# DC309A_Pinout.net
KiCad netlist of a schematic drawn in Altium Designer
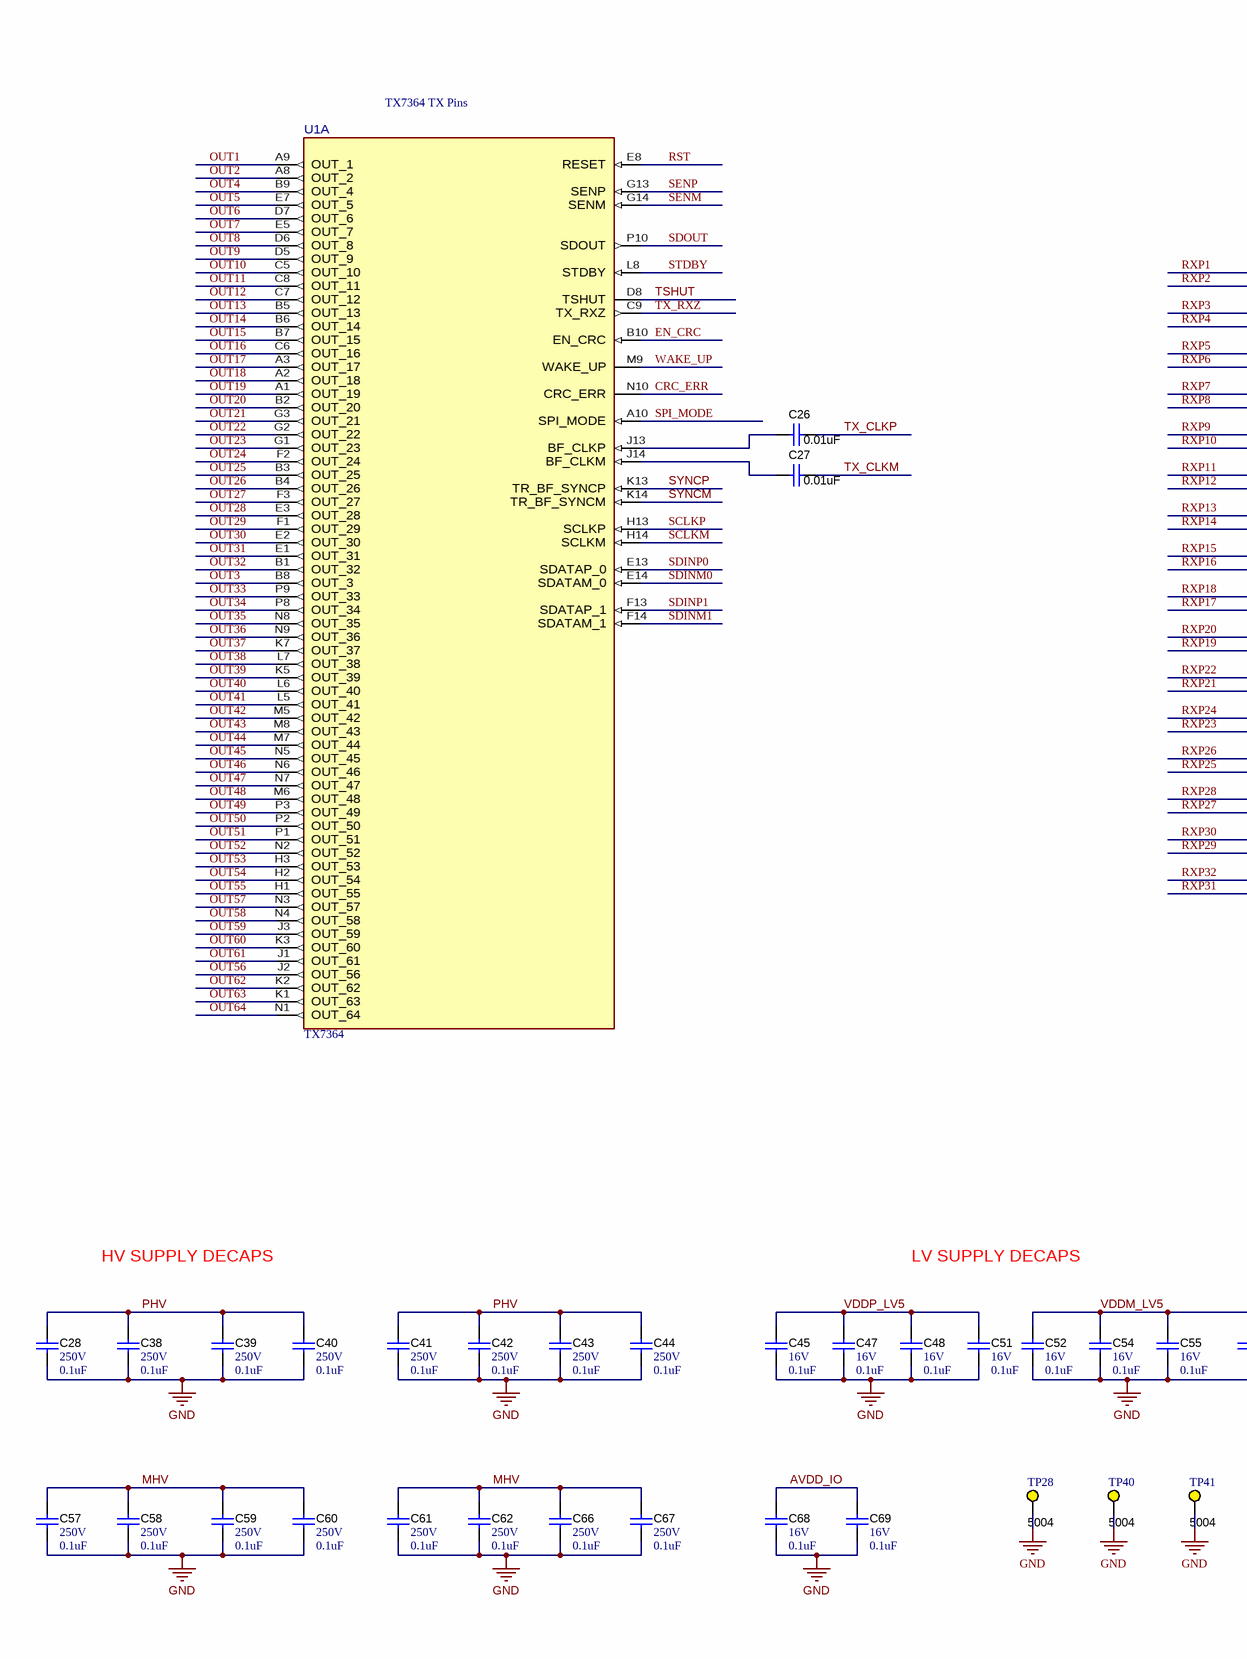
[diagram p0: DC309A_Pinout.SchDoc, left]
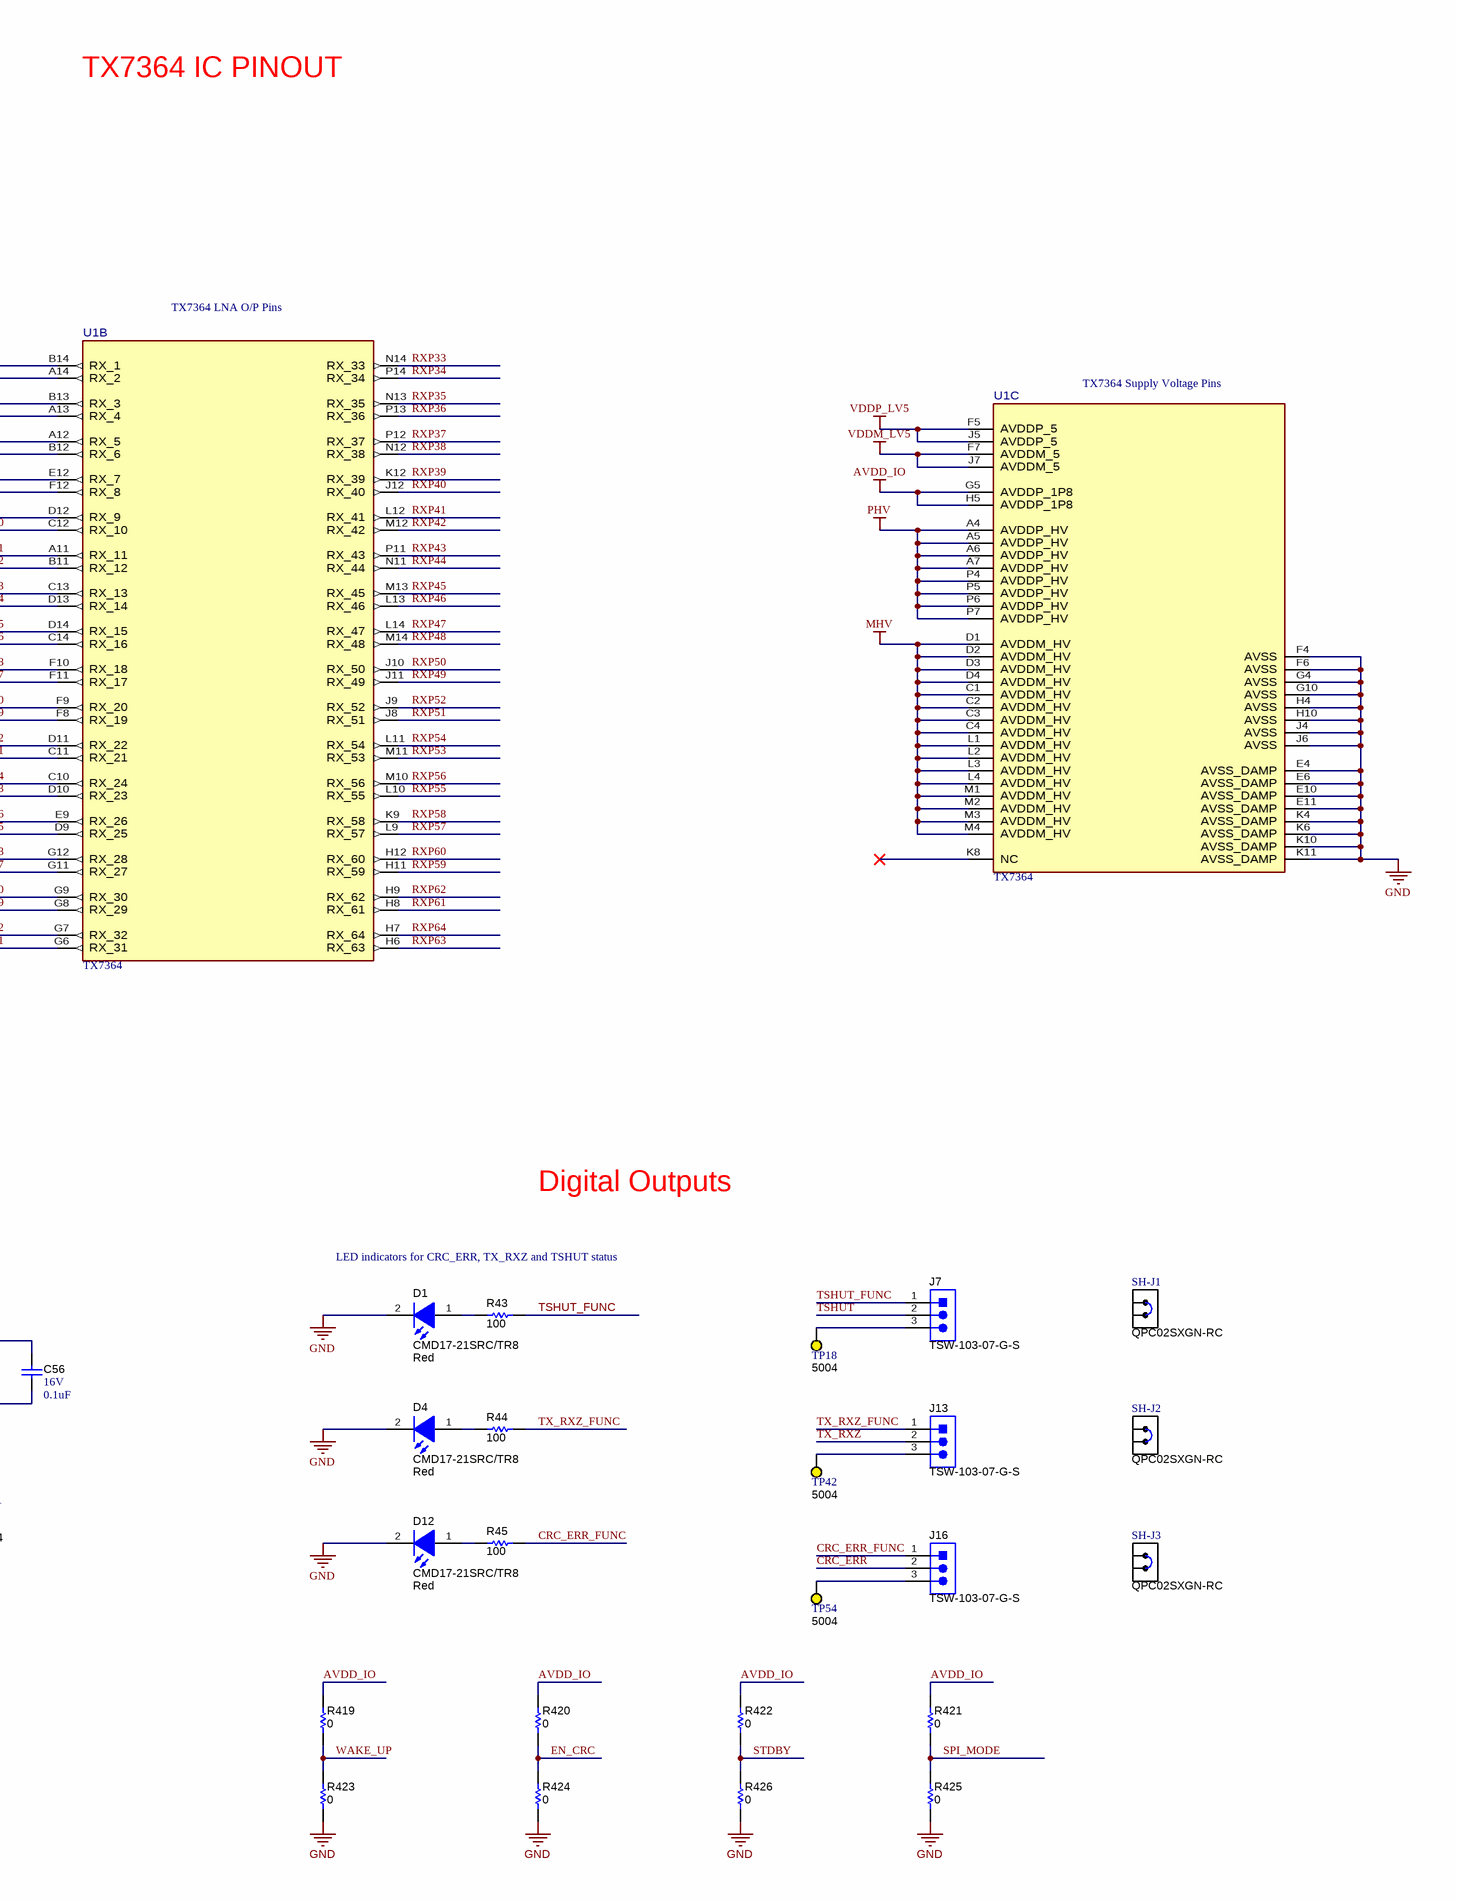
[diagram p1: DC309A_Pinout.SchDoc, right]

(export (version "E")
  (design (tool "Eeschema 10.0.6"))
  (components
    (comp (ref "C26")
      (value "520L103KT16T")
      (footprint "0402_065")
      (description "CAP, CERM, 0.01 uF, 16 V, +/- 10%, X7R, 0402")
      (fields (field (name "MANUFACTURER") "AT Ceramics") (field (name "VALUEDISPLAYED") "0.01uF"))
      (libsource (lib "Altium Vault - TI") (part "CMP-0006210-2"))
    )
    (comp (ref "C27")
      (value "520L103KT16T")
      (footprint "0402_065")
      (description "CAP, CERM, 0.01 uF, 16 V, +/- 10%, X7R, 0402")
      (fields (field (name "MANUFACTURER") "AT Ceramics") (field (name "VALUEDISPLAYED") "0.01uF"))
      (libsource (lib "Altium Vault - TI") (part "CMP-0006210-2"))
    )
    (comp (ref "C28")
      (value "C2012X7T2E104K125AA")
      (footprint "0805_HV")
      (description "CAP, CERM, 0.1 uF, 250 V, +/- 10%, X7T, 0805")
      (fields
        (field (name "MANUFACTURER") "TDK")
        (field (name "VDC_V") "250V")
        (field (name "VALUEDISPLAYED") "0.1uF")
      )
      (libsource (lib "Altium Vault - TI") (part "Capacitor"))
    )
    (comp (ref "C38")
      (value "C2012X7T2E104K125AA")
      (footprint "0805_HV")
      (description "CAP, CERM, 0.1 uF, 250 V, +/- 10%, X7T, 0805")
      (fields
        (field (name "MANUFACTURER") "TDK")
        (field (name "VDC_V") "250V")
        (field (name "VALUEDISPLAYED") "0.1uF")
      )
      (libsource (lib "Altium Vault - TI") (part "Capacitor"))
    )
    (comp (ref "C39")
      (value "C2012X7T2E104K125AA")
      (footprint "0805_HV")
      (description "CAP, CERM, 0.1 uF, 250 V, +/- 10%, X7T, 0805")
      (fields
        (field (name "MANUFACTURER") "TDK")
        (field (name "VDC_V") "250V")
        (field (name "VALUEDISPLAYED") "0.1uF")
      )
      (libsource (lib "Altium Vault - TI") (part "Capacitor"))
    )
    (comp (ref "C40")
      (value "C2012X7T2E104K125AA")
      (footprint "0805_HV")
      (description "CAP, CERM, 0.1 uF, 250 V, +/- 10%, X7T, 0805")
      (fields
        (field (name "MANUFACTURER") "TDK")
        (field (name "VDC_V") "250V")
        (field (name "VALUEDISPLAYED") "0.1uF")
      )
      (libsource (lib "Altium Vault - TI") (part "Capacitor"))
    )
    (comp (ref "C41")
      (value "C2012X7T2E104K125AA")
      (footprint "0805_HV")
      (description "CAP, CERM, 0.1 uF, 250 V, +/- 10%, X7T, 0805")
      (fields
        (field (name "MANUFACTURER") "TDK")
        (field (name "VDC_V") "250V")
        (field (name "VALUEDISPLAYED") "0.1uF")
      )
      (libsource (lib "Altium Vault - TI") (part "Capacitor"))
    )
    (comp (ref "C42")
      (value "C2012X7T2E104K125AA")
      (footprint "0805_HV")
      (description "CAP, CERM, 0.1 uF, 250 V, +/- 10%, X7T, 0805")
      (fields
        (field (name "MANUFACTURER") "TDK")
        (field (name "VDC_V") "250V")
        (field (name "VALUEDISPLAYED") "0.1uF")
      )
      (libsource (lib "Altium Vault - TI") (part "Capacitor"))
    )
    (comp (ref "C43")
      (value "C2012X7T2E104K125AA")
      (footprint "0805_HV")
      (description "CAP, CERM, 0.1 uF, 250 V, +/- 10%, X7T, 0805")
      (fields
        (field (name "MANUFACTURER") "TDK")
        (field (name "VDC_V") "250V")
        (field (name "VALUEDISPLAYED") "0.1uF")
      )
      (libsource (lib "Altium Vault - TI") (part "Capacitor"))
    )
    (comp (ref "C44")
      (value "C2012X7T2E104K125AA")
      (footprint "0805_HV")
      (description "CAP, CERM, 0.1 uF, 250 V, +/- 10%, X7T, 0805")
      (fields
        (field (name "MANUFACTURER") "TDK")
        (field (name "VDC_V") "250V")
        (field (name "VALUEDISPLAYED") "0.1uF")
      )
      (libsource (lib "Altium Vault - TI") (part "Capacitor"))
    )
    (comp (ref "C45")
      (value "C0603X6S1C104K030BC")
      (footprint "0201_033")
      (description "CAP, CERM, 0.1 uF, 16 V, +/- 10%, X6S, 0201")
      (fields
        (field (name "MANUFACTURER") "TDK")
        (field (name "VDC_V") "16V")
        (field (name "VALUEDISPLAYED") "0.1uF")
      )
      (libsource (lib "Altium Vault - TI") (part "Capacitor"))
    )
    (comp (ref "C47")
      (value "C0603X6S1C104K030BC")
      (footprint "0201_033")
      (description "CAP, CERM, 0.1 uF, 16 V, +/- 10%, X6S, 0201")
      (fields
        (field (name "MANUFACTURER") "TDK")
        (field (name "VDC_V") "16V")
        (field (name "VALUEDISPLAYED") "0.1uF")
      )
      (libsource (lib "Altium Vault - TI") (part "Capacitor"))
    )
    (comp (ref "C48")
      (value "C0603X6S1C104K030BC")
      (footprint "0201_033")
      (description "CAP, CERM, 0.1 uF, 16 V, +/- 10%, X6S, 0201")
      (fields
        (field (name "MANUFACTURER") "TDK")
        (field (name "VDC_V") "16V")
        (field (name "VALUEDISPLAYED") "0.1uF")
      )
      (libsource (lib "Altium Vault - TI") (part "Capacitor"))
    )
    (comp (ref "C51")
      (value "C0603X6S1C104K030BC")
      (footprint "0201_033")
      (description "CAP, CERM, 0.1 uF, 16 V, +/- 10%, X6S, 0201")
      (fields
        (field (name "MANUFACTURER") "TDK")
        (field (name "VDC_V") "16V")
        (field (name "VALUEDISPLAYED") "0.1uF")
      )
      (libsource (lib "Altium Vault - TI") (part "Capacitor"))
    )
    (comp (ref "C52")
      (value "C0603X6S1C104K030BC")
      (footprint "0201_033")
      (description "CAP, CERM, 0.1 uF, 16 V, +/- 10%, X6S, 0201")
      (fields
        (field (name "MANUFACTURER") "TDK")
        (field (name "VDC_V") "16V")
        (field (name "VALUEDISPLAYED") "0.1uF")
      )
      (libsource (lib "Altium Vault - TI") (part "Capacitor"))
    )
    (comp (ref "C54")
      (value "C0603X6S1C104K030BC")
      (footprint "0201_033")
      (description "CAP, CERM, 0.1 uF, 16 V, +/- 10%, X6S, 0201")
      (fields
        (field (name "MANUFACTURER") "TDK")
        (field (name "VDC_V") "16V")
        (field (name "VALUEDISPLAYED") "0.1uF")
      )
      (libsource (lib "Altium Vault - TI") (part "Capacitor"))
    )
    (comp (ref "C55")
      (value "C0603X6S1C104K030BC")
      (footprint "0201_033")
      (description "CAP, CERM, 0.1 uF, 16 V, +/- 10%, X6S, 0201")
      (fields
        (field (name "MANUFACTURER") "TDK")
        (field (name "VDC_V") "16V")
        (field (name "VALUEDISPLAYED") "0.1uF")
      )
      (libsource (lib "Altium Vault - TI") (part "Capacitor"))
    )
    (comp (ref "C56")
      (value "C0603X6S1C104K030BC")
      (footprint "0201_033")
      (description "CAP, CERM, 0.1 uF, 16 V, +/- 10%, X6S, 0201")
      (fields
        (field (name "MANUFACTURER") "TDK")
        (field (name "VDC_V") "16V")
        (field (name "VALUEDISPLAYED") "0.1uF")
      )
      (libsource (lib "Altium Vault - TI") (part "Capacitor"))
    )
    (comp (ref "C57")
      (value "C2012X7T2E104K125AA")
      (footprint "0805_HV")
      (description "CAP, CERM, 0.1 uF, 250 V, +/- 10%, X7T, 0805")
      (fields
        (field (name "MANUFACTURER") "TDK")
        (field (name "VDC_V") "250V")
        (field (name "VALUEDISPLAYED") "0.1uF")
      )
      (libsource (lib "Altium Vault - TI") (part "Capacitor"))
    )
    (comp (ref "C58")
      (value "C2012X7T2E104K125AA")
      (footprint "0805_HV")
      (description "CAP, CERM, 0.1 uF, 250 V, +/- 10%, X7T, 0805")
      (fields
        (field (name "MANUFACTURER") "TDK")
        (field (name "VDC_V") "250V")
        (field (name "VALUEDISPLAYED") "0.1uF")
      )
      (libsource (lib "Altium Vault - TI") (part "Capacitor"))
    )
    (comp (ref "C59")
      (value "C2012X7T2E104K125AA")
      (footprint "0805_HV")
      (description "CAP, CERM, 0.1 uF, 250 V, +/- 10%, X7T, 0805")
      (fields
        (field (name "MANUFACTURER") "TDK")
        (field (name "VDC_V") "250V")
        (field (name "VALUEDISPLAYED") "0.1uF")
      )
      (libsource (lib "Altium Vault - TI") (part "Capacitor"))
    )
    (comp (ref "C60")
      (value "C2012X7T2E104K125AA")
      (footprint "0805_HV")
      (description "CAP, CERM, 0.1 uF, 250 V, +/- 10%, X7T, 0805")
      (fields
        (field (name "MANUFACTURER") "TDK")
        (field (name "VDC_V") "250V")
        (field (name "VALUEDISPLAYED") "0.1uF")
      )
      (libsource (lib "Altium Vault - TI") (part "Capacitor"))
    )
    (comp (ref "C61")
      (value "C2012X7T2E104K125AA")
      (footprint "0805_HV")
      (description "CAP, CERM, 0.1 uF, 250 V, +/- 10%, X7T, 0805")
      (fields
        (field (name "MANUFACTURER") "TDK")
        (field (name "VDC_V") "250V")
        (field (name "VALUEDISPLAYED") "0.1uF")
      )
      (libsource (lib "Altium Vault - TI") (part "Capacitor"))
    )
    (comp (ref "C62")
      (value "C2012X7T2E104K125AA")
      (footprint "0805_HV")
      (description "CAP, CERM, 0.1 uF, 250 V, +/- 10%, X7T, 0805")
      (fields
        (field (name "MANUFACTURER") "TDK")
        (field (name "VDC_V") "250V")
        (field (name "VALUEDISPLAYED") "0.1uF")
      )
      (libsource (lib "Altium Vault - TI") (part "Capacitor"))
    )
    (comp (ref "C66")
      (value "C2012X7T2E104K125AA")
      (footprint "0805_HV")
      (description "CAP, CERM, 0.1 uF, 250 V, +/- 10%, X7T, 0805")
      (fields
        (field (name "MANUFACTURER") "TDK")
        (field (name "VDC_V") "250V")
        (field (name "VALUEDISPLAYED") "0.1uF")
      )
      (libsource (lib "Altium Vault - TI") (part "Capacitor"))
    )
    (comp (ref "C67")
      (value "C2012X7T2E104K125AA")
      (footprint "0805_HV")
      (description "CAP, CERM, 0.1 uF, 250 V, +/- 10%, X7T, 0805")
      (fields
        (field (name "MANUFACTURER") "TDK")
        (field (name "VDC_V") "250V")
        (field (name "VALUEDISPLAYED") "0.1uF")
      )
      (libsource (lib "Altium Vault - TI") (part "Capacitor"))
    )
    (comp (ref "C68")
      (value "C0603X6S1C104K030BC")
      (footprint "0201_033")
      (description "CAP, CERM, 0.1 uF, 16 V, +/- 10%, X6S, 0201")
      (fields
        (field (name "MANUFACTURER") "TDK")
        (field (name "VDC_V") "16V")
        (field (name "VALUEDISPLAYED") "0.1uF")
      )
      (libsource (lib "Altium Vault - TI") (part "Capacitor"))
    )
    (comp (ref "C69")
      (value "C0603X6S1C104K030BC")
      (footprint "0201_033")
      (description "CAP, CERM, 0.1 uF, 16 V, +/- 10%, X6S, 0201")
      (fields
        (field (name "MANUFACTURER") "TDK")
        (field (name "VDC_V") "16V")
        (field (name "VALUEDISPLAYED") "0.1uF")
      )
      (libsource (lib "Altium Vault - TI") (part "Capacitor"))
    )
    (comp (ref "D1")
      (value "CMD17-21SRC/TR8")
      (footprint "CMD17-21_Red")
      (description "LED, Red, SMD")
      (fields
        (field (name "ALTIUM_VALUE") "Red")
        (field (name "MANUFACTURER") "Visual Communications Company, LLC")
      )
      (libsource (lib "Altium Vault - TI") (part "CMP-0084855-1"))
    )
    (comp (ref "D4")
      (value "CMD17-21SRC/TR8")
      (footprint "CMD17-21_Red")
      (description "LED, Red, SMD")
      (fields
        (field (name "ALTIUM_VALUE") "Red")
        (field (name "MANUFACTURER") "Visual Communications Company, LLC")
      )
      (libsource (lib "Altium Vault - TI") (part "CMP-0084855-1"))
    )
    (comp (ref "D12")
      (value "CMD17-21SRC/TR8")
      (footprint "CMD17-21_Red")
      (description "LED, Red, SMD")
      (fields
        (field (name "ALTIUM_VALUE") "Red")
        (field (name "MANUFACTURER") "Visual Communications Company, LLC")
      )
      (libsource (lib "Altium Vault - TI") (part "CMP-0084855-1"))
    )
    (comp (ref "J7")
      (value "TSW-103-07-G-S")
      (footprint "TSW-103-07-G-S")
      (description "Header, 100mil, 3x1, Gold, TH")
      (fields (field (name "MANUFACTURER") "Samtec"))
      (libsource (lib "Altium Vault - TI") (part "Header_3x1"))
    )
    (comp (ref "J13")
      (value "TSW-103-07-G-S")
      (footprint "TSW-103-07-G-S")
      (description "Header, 100mil, 3x1, Gold, TH")
      (fields (field (name "MANUFACTURER") "Samtec"))
      (libsource (lib "Altium Vault - TI") (part "Header_3x1"))
    )
    (comp (ref "J16")
      (value "TSW-103-07-G-S")
      (footprint "TSW-103-07-G-S")
      (description "Header, 100mil, 3x1, Gold, TH")
      (fields (field (name "MANUFACTURER") "Samtec"))
      (libsource (lib "Altium Vault - TI") (part "Header_3x1"))
    )
    (comp (ref "R43")
      (value "Resistor")
      (footprint "0402")
      (description "RES, 100, 5%, 0.1 W, AEC-Q200 Grade 0, 0402")
      (fields
        (field (name "PARTNUMBER") "ERJ-2GEJ101X")
        (field (name "VALUEDISPLAYED") "100")
        (field (name "MANUFACTURER") "Panasonic")
      )
      (libsource (lib "Altium Vault - TI") (part "Resistor"))
    )
    (comp (ref "R44")
      (value "Resistor")
      (footprint "0402")
      (description "RES, 100, 5%, 0.1 W, AEC-Q200 Grade 0, 0402")
      (fields
        (field (name "PARTNUMBER") "ERJ-2GEJ101X")
        (field (name "VALUEDISPLAYED") "100")
        (field (name "MANUFACTURER") "Panasonic")
      )
      (libsource (lib "Altium Vault - TI") (part "Resistor"))
    )
    (comp (ref "R45")
      (value "Resistor")
      (footprint "0402")
      (description "RES, 100, 5%, 0.1 W, AEC-Q200 Grade 0, 0402")
      (fields
        (field (name "PARTNUMBER") "ERJ-2GEJ101X")
        (field (name "VALUEDISPLAYED") "100")
        (field (name "MANUFACTURER") "Panasonic")
      )
      (libsource (lib "Altium Vault - TI") (part "Resistor"))
    )
    (comp (ref "R419")
      (value "Resistor")
      (footprint "0402")
      (description "RES, 0, 5%, 0.1 W, AEC-Q200 Grade 0, 0402")
      (fields
        (field (name "PARTNUMBER") "ERJ-2GE0R00X")
        (field (name "MANUFACTURER") "Panasonic")
        (field (name "RES_OHM") "0")
      )
      (libsource (lib "Altium Vault - TI") (part "CMP-0026992-3"))
    )
    (comp (ref "R420")
      (value "Resistor")
      (footprint "0402")
      (description "RES, 0, 5%, 0.1 W, AEC-Q200 Grade 0, 0402")
      (fields
        (field (name "PARTNUMBER") "ERJ-2GE0R00X")
        (field (name "MANUFACTURER") "Panasonic")
        (field (name "RES_OHM") "0")
      )
      (libsource (lib "Altium Vault - TI") (part "CMP-0026992-3"))
    )
    (comp (ref "R421")
      (value "Resistor")
      (footprint "0402")
      (description "RES, 0, 5%, 0.1 W, AEC-Q200 Grade 0, 0402")
      (fields
        (field (name "PARTNUMBER") "ERJ-2GE0R00X")
        (field (name "MANUFACTURER") "Panasonic")
        (field (name "RES_OHM") "0")
      )
      (libsource (lib "Altium Vault - TI") (part "CMP-0026992-3"))
    )
    (comp (ref "R422")
      (value "Resistor")
      (footprint "0402")
      (description "RES, 0, 5%, 0.1 W, AEC-Q200 Grade 0, 0402")
      (fields
        (field (name "PARTNUMBER") "ERJ-2GE0R00X")
        (field (name "MANUFACTURER") "Panasonic")
        (field (name "RES_OHM") "0")
      )
      (libsource (lib "Altium Vault - TI") (part "CMP-0026992-3"))
    )
    (comp (ref "R423")
      (value "Resistor")
      (footprint "0402")
      (description "RES, 0, 5%, 0.1 W, AEC-Q200 Grade 0, 0402")
      (fields
        (field (name "PARTNUMBER") "ERJ-2GE0R00X")
        (field (name "MANUFACTURER") "Panasonic")
        (field (name "RES_OHM") "0")
      )
      (libsource (lib "Altium Vault - TI") (part "CMP-0026992-3"))
    )
    (comp (ref "R424")
      (value "Resistor")
      (footprint "0402")
      (description "RES, 0, 5%, 0.1 W, AEC-Q200 Grade 0, 0402")
      (fields
        (field (name "PARTNUMBER") "ERJ-2GE0R00X")
        (field (name "MANUFACTURER") "Panasonic")
        (field (name "RES_OHM") "0")
      )
      (libsource (lib "Altium Vault - TI") (part "CMP-0026992-3"))
    )
    (comp (ref "R425")
      (value "Resistor")
      (footprint "0402")
      (description "RES, 0, 5%, 0.1 W, AEC-Q200 Grade 0, 0402")
      (fields
        (field (name "PARTNUMBER") "ERJ-2GE0R00X")
        (field (name "MANUFACTURER") "Panasonic")
        (field (name "RES_OHM") "0")
      )
      (libsource (lib "Altium Vault - TI") (part "CMP-0026992-3"))
    )
    (comp (ref "R426")
      (value "Resistor")
      (footprint "0402")
      (description "RES, 0, 5%, 0.1 W, AEC-Q200 Grade 0, 0402")
      (fields
        (field (name "PARTNUMBER") "ERJ-2GE0R00X")
        (field (name "MANUFACTURER") "Panasonic")
        (field (name "RES_OHM") "0")
      )
      (libsource (lib "Altium Vault - TI") (part "CMP-0026992-3"))
    )
    (comp (ref "SH-J1")
      (value "QPC02SXGN-RC")
      (footprint "FP-QPC02SXGN-RC_JUMPER-MFG")
      (fields (field (name "MANUFACTURER") "Sullins"))
      (libsource (lib "Altium Vault - TI") (part "Shunt"))
    )
    (comp (ref "SH-J2")
      (value "QPC02SXGN-RC")
      (footprint "FP-QPC02SXGN-RC_JUMPER-MFG")
      (fields (field (name "MANUFACTURER") "Sullins"))
      (libsource (lib "Altium Vault - TI") (part "Shunt"))
    )
    (comp (ref "SH-J3")
      (value "QPC02SXGN-RC")
      (footprint "FP-QPC02SXGN-RC_JUMPER-MFG")
      (fields (field (name "MANUFACTURER") "Sullins"))
      (libsource (lib "Altium Vault - TI") (part "Shunt"))
    )
    (comp (ref "TP18")
      (value "5004")
      (footprint "Keystone5004")
      (description "Test Point, Miniature, Yellow, TH")
      (fields (field (name "MANUFACTURER") "Keystone Electronics"))
      (libsource (lib "Altium Vault - TI") (part "5004"))
    )
    (comp (ref "TP28")
      (value "5004")
      (footprint "Keystone5004")
      (description "Test Point, Miniature, Yellow, TH")
      (fields (field (name "MANUFACTURER") "Keystone Electronics"))
      (libsource (lib "Altium Vault - TI") (part "5004"))
    )
    (comp (ref "TP40")
      (value "5004")
      (footprint "Keystone5004")
      (description "Test Point, Miniature, Yellow, TH")
      (fields (field (name "MANUFACTURER") "Keystone Electronics"))
      (libsource (lib "Altium Vault - TI") (part "5004"))
    )
    (comp (ref "TP41")
      (value "5004")
      (footprint "Keystone5004")
      (description "Test Point, Miniature, Yellow, TH")
      (fields (field (name "MANUFACTURER") "Keystone Electronics"))
      (libsource (lib "Altium Vault - TI") (part "5004"))
    )
    (comp (ref "TP42")
      (value "5004")
      (footprint "Keystone5004")
      (description "Test Point, Miniature, Yellow, TH")
      (fields (field (name "MANUFACTURER") "Keystone Electronics"))
      (libsource (lib "Altium Vault - TI") (part "5004"))
    )
    (comp (ref "TP54")
      (value "5004")
      (footprint "Keystone5004")
      (description "Test Point, Miniature, Yellow, TH")
      (fields (field (name "MANUFACTURER") "Keystone Electronics"))
      (libsource (lib "Altium Vault - TI") (part "5004"))
    )
    (comp (ref "U1")
      (value "TX7364")
      (footprint "ACP0196A-MFG")
      (fields (field (name "PARTNUMBER") "TX7364") (field (name "MANUFACTURER") "Texas Instruments"))
      (libsource (lib "Altium Vault - TI") (part "SYM-TX7364"))
    )
  )
  (nets
    (net (code "1") (name "/CRC_ERR") (class "Default")
      (node (ref "J16") (pin "2") (pinfunction "2_2") (pintype "passive"))
      (node (ref "U1") (pin "N10") (pinfunction "CRC_ERR_N10") (pintype "passive"))
    )
    (net (code "2") (name "/CRC_ERR_FUNC") (class "Default")
      (node (ref "J16") (pin "1") (pinfunction "1_1") (pintype "passive"))
      (node (ref "R45") (pin "1") (pinfunction "1_1") (pintype "passive"))
    )
    (net (code "3") (name "/EN_CRC") (class "Default")
      (node (ref "R420") (pin "1") (pinfunction "1_1") (pintype "passive"))
      (node (ref "R424") (pin "2") (pinfunction "2_2") (pintype "passive"))
      (node (ref "U1") (pin "B10") (pinfunction "EN_CRC_B10") (pintype "input"))
    )
    (net (code "4") (name "/OUT1") (class "Default")
      (node (ref "U1") (pin "A9") (pinfunction "OUT_1_A9") (pintype "output"))
    )
    (net (code "5") (name "/OUT2") (class "Default")
      (node (ref "U1") (pin "A8") (pinfunction "OUT_2_A8") (pintype "output"))
    )
    (net (code "6") (name "/OUT3") (class "Default")
      (node (ref "U1") (pin "B8") (pinfunction "OUT_3_B8") (pintype "output"))
    )
    (net (code "7") (name "/OUT4") (class "Default")
      (node (ref "U1") (pin "B9") (pinfunction "OUT_4_B9") (pintype "output"))
    )
    (net (code "8") (name "/OUT5") (class "Default")
      (node (ref "U1") (pin "E7") (pinfunction "OUT_5_E7") (pintype "output"))
    )
    (net (code "9") (name "/OUT6") (class "Default")
      (node (ref "U1") (pin "D7") (pinfunction "OUT_6_D7") (pintype "output"))
    )
    (net (code "10") (name "/OUT7") (class "Default")
      (node (ref "U1") (pin "E5") (pinfunction "OUT_7_E5") (pintype "output"))
    )
    (net (code "11") (name "/OUT8") (class "Default")
      (node (ref "U1") (pin "D6") (pinfunction "OUT_8_D6") (pintype "output"))
    )
    (net (code "12") (name "/OUT9") (class "Default")
      (node (ref "U1") (pin "D5") (pinfunction "OUT_9_D5") (pintype "output"))
    )
    (net (code "13") (name "/OUT10") (class "Default")
      (node (ref "U1") (pin "C5") (pinfunction "OUT_10_C5") (pintype "output"))
    )
    (net (code "14") (name "/OUT11") (class "Default")
      (node (ref "U1") (pin "C8") (pinfunction "OUT_11_C8") (pintype "output"))
    )
    (net (code "15") (name "/OUT12") (class "Default")
      (node (ref "U1") (pin "C7") (pinfunction "OUT_12_C7") (pintype "output"))
    )
    (net (code "16") (name "/OUT13") (class "Default")
      (node (ref "U1") (pin "B5") (pinfunction "OUT_13_B5") (pintype "output"))
    )
    (net (code "17") (name "/OUT14") (class "Default")
      (node (ref "U1") (pin "B6") (pinfunction "OUT_14_B6") (pintype "output"))
    )
    (net (code "18") (name "/OUT15") (class "Default")
      (node (ref "U1") (pin "B7") (pinfunction "OUT_15_B7") (pintype "output"))
    )
    (net (code "19") (name "/OUT16") (class "Default")
      (node (ref "U1") (pin "C6") (pinfunction "OUT_16_C6") (pintype "output"))
    )
    (net (code "20") (name "/OUT17") (class "Default")
      (node (ref "U1") (pin "A3") (pinfunction "OUT_17_A3") (pintype "output"))
    )
    (net (code "21") (name "/OUT18") (class "Default")
      (node (ref "U1") (pin "A2") (pinfunction "OUT_18_A2") (pintype "output"))
    )
    (net (code "22") (name "/OUT19") (class "Default")
      (node (ref "U1") (pin "A1") (pinfunction "OUT_19_A1") (pintype "output"))
    )
    (net (code "23") (name "/OUT20") (class "Default")
      (node (ref "U1") (pin "B2") (pinfunction "OUT_20_B2") (pintype "output"))
    )
    (net (code "24") (name "/OUT21") (class "Default")
      (node (ref "U1") (pin "G3") (pinfunction "OUT_21_G3") (pintype "output"))
    )
    (net (code "25") (name "/OUT22") (class "Default")
      (node (ref "U1") (pin "G2") (pinfunction "OUT_22_G2") (pintype "output"))
    )
    (net (code "26") (name "/OUT23") (class "Default")
      (node (ref "U1") (pin "G1") (pinfunction "OUT_23_G1") (pintype "output"))
    )
    (net (code "27") (name "/OUT24") (class "Default")
      (node (ref "U1") (pin "F2") (pinfunction "OUT_24_F2") (pintype "output"))
    )
    (net (code "28") (name "/OUT25") (class "Default")
      (node (ref "U1") (pin "B3") (pinfunction "OUT_25_B3") (pintype "output"))
    )
    (net (code "29") (name "/OUT26") (class "Default")
      (node (ref "U1") (pin "B4") (pinfunction "OUT_26_B4") (pintype "output"))
    )
    (net (code "30") (name "/OUT27") (class "Default")
      (node (ref "U1") (pin "F3") (pinfunction "OUT_27_F3") (pintype "output"))
    )
    (net (code "31") (name "/OUT28") (class "Default")
      (node (ref "U1") (pin "E3") (pinfunction "OUT_28_E3") (pintype "output"))
    )
    (net (code "32") (name "/OUT29") (class "Default")
      (node (ref "U1") (pin "F1") (pinfunction "OUT_29_F1") (pintype "output"))
    )
    (net (code "33") (name "/OUT30") (class "Default")
      (node (ref "U1") (pin "E2") (pinfunction "OUT_30_E2") (pintype "output"))
    )
    (net (code "34") (name "/OUT31") (class "Default")
      (node (ref "U1") (pin "E1") (pinfunction "OUT_31_E1") (pintype "output"))
    )
    (net (code "35") (name "/OUT32") (class "Default")
      (node (ref "U1") (pin "B1") (pinfunction "OUT_32_B1") (pintype "output"))
    )
    (net (code "36") (name "/OUT33") (class "Default")
      (node (ref "U1") (pin "P9") (pinfunction "OUT_33_P9") (pintype "output"))
    )
    (net (code "37") (name "/OUT34") (class "Default")
      (node (ref "U1") (pin "P8") (pinfunction "OUT_34_P8") (pintype "output"))
    )
    (net (code "38") (name "/OUT35") (class "Default")
      (node (ref "U1") (pin "N8") (pinfunction "OUT_35_N8") (pintype "output"))
    )
    (net (code "39") (name "/OUT36") (class "Default")
      (node (ref "U1") (pin "N9") (pinfunction "OUT_36_N9") (pintype "output"))
    )
    (net (code "40") (name "/OUT37") (class "Default")
      (node (ref "U1") (pin "K7") (pinfunction "OUT_37_K7") (pintype "output"))
    )
    (net (code "41") (name "/OUT38") (class "Default")
      (node (ref "U1") (pin "L7") (pinfunction "OUT_38_L7") (pintype "output"))
    )
    (net (code "42") (name "/OUT39") (class "Default")
      (node (ref "U1") (pin "K5") (pinfunction "OUT_39_K5") (pintype "output"))
    )
    (net (code "43") (name "/OUT40") (class "Default")
      (node (ref "U1") (pin "L6") (pinfunction "OUT_40_L6") (pintype "output"))
    )
    (net (code "44") (name "/OUT41") (class "Default")
      (node (ref "U1") (pin "L5") (pinfunction "OUT_41_L5") (pintype "output"))
    )
    (net (code "45") (name "/OUT42") (class "Default")
      (node (ref "U1") (pin "M5") (pinfunction "OUT_42_M5") (pintype "output"))
    )
    (net (code "46") (name "/OUT43") (class "Default")
      (node (ref "U1") (pin "M8") (pinfunction "OUT_43_M8") (pintype "output"))
    )
    (net (code "47") (name "/OUT44") (class "Default")
      (node (ref "U1") (pin "M7") (pinfunction "OUT_44_M7") (pintype "output"))
    )
    (net (code "48") (name "/OUT45") (class "Default")
      (node (ref "U1") (pin "N5") (pinfunction "OUT_45_N5") (pintype "output"))
    )
    (net (code "49") (name "/OUT46") (class "Default")
      (node (ref "U1") (pin "N6") (pinfunction "OUT_46_N6") (pintype "output"))
    )
    (net (code "50") (name "/OUT47") (class "Default")
      (node (ref "U1") (pin "N7") (pinfunction "OUT_47_N7") (pintype "output"))
    )
    (net (code "51") (name "/OUT48") (class "Default")
      (node (ref "U1") (pin "M6") (pinfunction "OUT_48_M6") (pintype "output"))
    )
    (net (code "52") (name "/OUT49") (class "Default")
      (node (ref "U1") (pin "P3") (pinfunction "OUT_49_P3") (pintype "output"))
    )
    (net (code "53") (name "/OUT50") (class "Default")
      (node (ref "U1") (pin "P2") (pinfunction "OUT_50_P2") (pintype "output"))
    )
    (net (code "54") (name "/OUT51") (class "Default")
      (node (ref "U1") (pin "P1") (pinfunction "OUT_51_P1") (pintype "output"))
    )
    (net (code "55") (name "/OUT52") (class "Default")
      (node (ref "U1") (pin "N2") (pinfunction "OUT_52_N2") (pintype "output"))
    )
    (net (code "56") (name "/OUT53") (class "Default")
      (node (ref "U1") (pin "H3") (pinfunction "OUT_53_H3") (pintype "output"))
    )
    (net (code "57") (name "/OUT54") (class "Default")
      (node (ref "U1") (pin "H2") (pinfunction "OUT_54_H2") (pintype "output"))
    )
    (net (code "58") (name "/OUT55") (class "Default")
      (node (ref "U1") (pin "H1") (pinfunction "OUT_55_H1") (pintype "output"))
    )
    (net (code "59") (name "/OUT56") (class "Default")
      (node (ref "U1") (pin "J2") (pinfunction "OUT_56_J2") (pintype "output"))
    )
    (net (code "60") (name "/OUT57") (class "Default")
      (node (ref "U1") (pin "N3") (pinfunction "OUT_57_N3") (pintype "output"))
    )
    (net (code "61") (name "/OUT58") (class "Default")
      (node (ref "U1") (pin "N4") (pinfunction "OUT_58_N4") (pintype "output"))
    )
    (net (code "62") (name "/OUT59") (class "Default")
      (node (ref "U1") (pin "J3") (pinfunction "OUT_59_J3") (pintype "output"))
    )
    (net (code "63") (name "/OUT60") (class "Default")
      (node (ref "U1") (pin "K3") (pinfunction "OUT_60_K3") (pintype "output"))
    )
    (net (code "64") (name "/OUT61") (class "Default")
      (node (ref "U1") (pin "J1") (pinfunction "OUT_61_J1") (pintype "output"))
    )
    (net (code "65") (name "/OUT62") (class "Default")
      (node (ref "U1") (pin "K2") (pinfunction "OUT_62_K2") (pintype "output"))
    )
    (net (code "66") (name "/OUT63") (class "Default")
      (node (ref "U1") (pin "K1") (pinfunction "OUT_63_K1") (pintype "output"))
    )
    (net (code "67") (name "/OUT64") (class "Default")
      (node (ref "U1") (pin "N1") (pinfunction "OUT_64_N1") (pintype "output"))
    )
    (net (code "68") (name "/RST") (class "Default")
      (node (ref "U1") (pin "E8") (pinfunction "RESET_E8") (pintype "input"))
    )
    (net (code "69") (name "/RXP1") (class "Default")
      (node (ref "U1") (pin "B14") (pinfunction "RX_1_B14") (pintype "output"))
    )
    (net (code "70") (name "/RXP2") (class "Default")
      (node (ref "U1") (pin "A14") (pinfunction "RX_2_A14") (pintype "output"))
    )
    (net (code "71") (name "/RXP3") (class "Default")
      (node (ref "U1") (pin "B13") (pinfunction "RX_3_B13") (pintype "output"))
    )
    (net (code "72") (name "/RXP4") (class "Default")
      (node (ref "U1") (pin "A13") (pinfunction "RX_4_A13") (pintype "output"))
    )
    (net (code "73") (name "/RXP5") (class "Default")
      (node (ref "U1") (pin "A12") (pinfunction "RX_5_A12") (pintype "output"))
    )
    (net (code "74") (name "/RXP6") (class "Default")
      (node (ref "U1") (pin "B12") (pinfunction "RX_6_B12") (pintype "output"))
    )
    (net (code "75") (name "/RXP7") (class "Default")
      (node (ref "U1") (pin "E12") (pinfunction "RX_7_E12") (pintype "output"))
    )
    (net (code "76") (name "/RXP8") (class "Default")
      (node (ref "U1") (pin "F12") (pinfunction "RX_8_F12") (pintype "output"))
    )
    (net (code "77") (name "/RXP9") (class "Default")
      (node (ref "U1") (pin "D12") (pinfunction "RX_9_D12") (pintype "output"))
    )
    (net (code "78") (name "/RXP10") (class "Default")
      (node (ref "U1") (pin "C12") (pinfunction "RX_10_C12") (pintype "output"))
    )
    (net (code "79") (name "/RXP11") (class "Default")
      (node (ref "U1") (pin "A11") (pinfunction "RX_11_A11") (pintype "output"))
    )
    (net (code "80") (name "/RXP12") (class "Default")
      (node (ref "U1") (pin "B11") (pinfunction "RX_12_B11") (pintype "output"))
    )
    (net (code "81") (name "/RXP13") (class "Default")
      (node (ref "U1") (pin "C13") (pinfunction "RX_13_C13") (pintype "output"))
    )
    (net (code "82") (name "/RXP14") (class "Default")
      (node (ref "U1") (pin "D13") (pinfunction "RX_14_D13") (pintype "output"))
    )
    (net (code "83") (name "/RXP15") (class "Default")
      (node (ref "U1") (pin "D14") (pinfunction "RX_15_D14") (pintype "output"))
    )
    (net (code "84") (name "/RXP16") (class "Default")
      (node (ref "U1") (pin "C14") (pinfunction "RX_16_C14") (pintype "output"))
    )
    (net (code "85") (name "/RXP17") (class "Default")
      (node (ref "U1") (pin "F11") (pinfunction "RX_17_F11") (pintype "output"))
    )
    (net (code "86") (name "/RXP18") (class "Default")
      (node (ref "U1") (pin "F10") (pinfunction "RX_18_F10") (pintype "output"))
    )
    (net (code "87") (name "/RXP19") (class "Default")
      (node (ref "U1") (pin "F8") (pinfunction "RX_19_F8") (pintype "output"))
    )
    (net (code "88") (name "/RXP20") (class "Default")
      (node (ref "U1") (pin "F9") (pinfunction "RX_20_F9") (pintype "output"))
    )
    (net (code "89") (name "/RXP21") (class "Default")
      (node (ref "U1") (pin "C11") (pinfunction "RX_21_C11") (pintype "output"))
    )
    (net (code "90") (name "/RXP22") (class "Default")
      (node (ref "U1") (pin "D11") (pinfunction "RX_22_D11") (pintype "output"))
    )
    (net (code "91") (name "/RXP23") (class "Default")
      (node (ref "U1") (pin "D10") (pinfunction "RX_23_D10") (pintype "output"))
    )
    (net (code "92") (name "/RXP24") (class "Default")
      (node (ref "U1") (pin "C10") (pinfunction "RX_24_C10") (pintype "output"))
    )
    (net (code "93") (name "/RXP25") (class "Default")
      (node (ref "U1") (pin "D9") (pinfunction "RX_25_D9") (pintype "output"))
    )
    (net (code "94") (name "/RXP26") (class "Default")
      (node (ref "U1") (pin "E9") (pinfunction "RX_26_E9") (pintype "output"))
    )
    (net (code "95") (name "/RXP27") (class "Default")
      (node (ref "U1") (pin "G11") (pinfunction "RX_27_G11") (pintype "output"))
    )
    (net (code "96") (name "/RXP28") (class "Default")
      (node (ref "U1") (pin "G12") (pinfunction "RX_28_G12") (pintype "output"))
    )
    (net (code "97") (name "/RXP29") (class "Default")
      (node (ref "U1") (pin "G8") (pinfunction "RX_29_G8") (pintype "output"))
    )
    (net (code "98") (name "/RXP30") (class "Default")
      (node (ref "U1") (pin "G9") (pinfunction "RX_30_G9") (pintype "output"))
    )
    (net (code "99") (name "/RXP31") (class "Default")
      (node (ref "U1") (pin "G6") (pinfunction "RX_31_G6") (pintype "output"))
    )
    (net (code "100") (name "/RXP32") (class "Default")
      (node (ref "U1") (pin "G7") (pinfunction "RX_32_G7") (pintype "output"))
    )
    (net (code "101") (name "/RXP33") (class "Default")
      (node (ref "U1") (pin "N14") (pinfunction "RX_33_N14") (pintype "output"))
    )
    (net (code "102") (name "/RXP34") (class "Default")
      (node (ref "U1") (pin "P14") (pinfunction "RX_34_P14") (pintype "output"))
    )
    (net (code "103") (name "/RXP35") (class "Default")
      (node (ref "U1") (pin "N13") (pinfunction "RX_35_N13") (pintype "output"))
    )
    (net (code "104") (name "/RXP36") (class "Default")
      (node (ref "U1") (pin "P13") (pinfunction "RX_36_P13") (pintype "output"))
    )
    (net (code "105") (name "/RXP37") (class "Default")
      (node (ref "U1") (pin "P12") (pinfunction "RX_37_P12") (pintype "output"))
    )
    (net (code "106") (name "/RXP38") (class "Default")
      (node (ref "U1") (pin "N12") (pinfunction "RX_38_N12") (pintype "output"))
    )
    (net (code "107") (name "/RXP39") (class "Default")
      (node (ref "U1") (pin "K12") (pinfunction "RX_39_K12") (pintype "output"))
    )
    (net (code "108") (name "/RXP40") (class "Default")
      (node (ref "U1") (pin "J12") (pinfunction "RX_40_J12") (pintype "output"))
    )
    (net (code "109") (name "/RXP41") (class "Default")
      (node (ref "U1") (pin "L12") (pinfunction "RX_41_L12") (pintype "output"))
    )
    (net (code "110") (name "/RXP42") (class "Default")
      (node (ref "U1") (pin "M12") (pinfunction "RX_42_M12") (pintype "output"))
    )
    (net (code "111") (name "/RXP43") (class "Default")
      (node (ref "U1") (pin "P11") (pinfunction "RX_43_P11") (pintype "output"))
    )
    (net (code "112") (name "/RXP44") (class "Default")
      (node (ref "U1") (pin "N11") (pinfunction "RX_44_N11") (pintype "output"))
    )
    (net (code "113") (name "/RXP45") (class "Default")
      (node (ref "U1") (pin "M13") (pinfunction "RX_45_M13") (pintype "output"))
    )
    (net (code "114") (name "/RXP46") (class "Default")
      (node (ref "U1") (pin "L13") (pinfunction "RX_46_L13") (pintype "output"))
    )
    (net (code "115") (name "/RXP47") (class "Default")
      (node (ref "U1") (pin "L14") (pinfunction "RX_47_L14") (pintype "output"))
    )
    (net (code "116") (name "/RXP48") (class "Default")
      (node (ref "U1") (pin "M14") (pinfunction "RX_48_M14") (pintype "output"))
    )
    (net (code "117") (name "/RXP49") (class "Default")
      (node (ref "U1") (pin "J11") (pinfunction "RX_49_J11") (pintype "output"))
    )
    (net (code "118") (name "/RXP50") (class "Default")
      (node (ref "U1") (pin "J10") (pinfunction "RX_50_J10") (pintype "output"))
    )
    (net (code "119") (name "/RXP51") (class "Default")
      (node (ref "U1") (pin "J8") (pinfunction "RX_51_J8") (pintype "output"))
    )
    (net (code "120") (name "/RXP52") (class "Default")
      (node (ref "U1") (pin "J9") (pinfunction "RX_52_J9") (pintype "output"))
    )
    (net (code "121") (name "/RXP53") (class "Default")
      (node (ref "U1") (pin "M11") (pinfunction "RX_53_M11") (pintype "output"))
    )
    (net (code "122") (name "/RXP54") (class "Default")
      (node (ref "U1") (pin "L11") (pinfunction "RX_54_L11") (pintype "output"))
    )
    (net (code "123") (name "/RXP55") (class "Default")
      (node (ref "U1") (pin "L10") (pinfunction "RX_55_L10") (pintype "output"))
    )
    (net (code "124") (name "/RXP56") (class "Default")
      (node (ref "U1") (pin "M10") (pinfunction "RX_56_M10") (pintype "output"))
    )
    (net (code "125") (name "/RXP57") (class "Default")
      (node (ref "U1") (pin "L9") (pinfunction "RX_57_L9") (pintype "output"))
    )
    (net (code "126") (name "/RXP58") (class "Default")
      (node (ref "U1") (pin "K9") (pinfunction "RX_58_K9") (pintype "output"))
    )
    (net (code "127") (name "/RXP59") (class "Default")
      (node (ref "U1") (pin "H11") (pinfunction "RX_59_H11") (pintype "output"))
    )
    (net (code "128") (name "/RXP60") (class "Default")
      (node (ref "U1") (pin "H12") (pinfunction "RX_60_H12") (pintype "output"))
    )
    (net (code "129") (name "/RXP61") (class "Default")
      (node (ref "U1") (pin "H8") (pinfunction "RX_61_H8") (pintype "output"))
    )
    (net (code "130") (name "/RXP62") (class "Default")
      (node (ref "U1") (pin "H9") (pinfunction "RX_62_H9") (pintype "output"))
    )
    (net (code "131") (name "/RXP63") (class "Default")
      (node (ref "U1") (pin "H6") (pinfunction "RX_63_H6") (pintype "output"))
    )
    (net (code "132") (name "/RXP64") (class "Default")
      (node (ref "U1") (pin "H7") (pinfunction "RX_64_H7") (pintype "output"))
    )
    (net (code "133") (name "/SCLKM") (class "Default")
      (node (ref "U1") (pin "H14") (pinfunction "SCLKM_H14") (pintype "input"))
    )
    (net (code "134") (name "/SCLKP") (class "Default")
      (node (ref "U1") (pin "H13") (pinfunction "SCLKP_H13") (pintype "input"))
    )
    (net (code "135") (name "/SDINM0") (class "Default")
      (node (ref "U1") (pin "E14") (pinfunction "SDATAM_0_E14") (pintype "input"))
    )
    (net (code "136") (name "/SDINM1") (class "Default")
      (node (ref "U1") (pin "F14") (pinfunction "SDATAM_1_F14") (pintype "input"))
    )
    (net (code "137") (name "/SDINP0") (class "Default")
      (node (ref "U1") (pin "E13") (pinfunction "SDATAP_0_E13") (pintype "input"))
    )
    (net (code "138") (name "/SDINP1") (class "Default")
      (node (ref "U1") (pin "F13") (pinfunction "SDATAP_1_F13") (pintype "input"))
    )
    (net (code "139") (name "/SDOUT") (class "Default")
      (node (ref "U1") (pin "P10") (pinfunction "SDOUT_P10") (pintype "output"))
    )
    (net (code "140") (name "/SENM") (class "Default")
      (node (ref "U1") (pin "G14") (pinfunction "SENM_G14") (pintype "input"))
    )
    (net (code "141") (name "/SENP") (class "Default")
      (node (ref "U1") (pin "G13") (pinfunction "SENP_G13") (pintype "input"))
    )
    (net (code "142") (name "/SPI_MODE") (class "Default")
      (node (ref "R421") (pin "1") (pinfunction "1_1") (pintype "passive"))
      (node (ref "R425") (pin "2") (pinfunction "2_2") (pintype "passive"))
      (node (ref "U1") (pin "A10") (pinfunction "SPI_MODE_A10") (pintype "input"))
    )
    (net (code "143") (name "/STDBY") (class "Default")
      (node (ref "R422") (pin "1") (pinfunction "1_1") (pintype "passive"))
      (node (ref "R426") (pin "2") (pinfunction "2_2") (pintype "passive"))
      (node (ref "U1") (pin "L8") (pinfunction "STDBY_L8") (pintype "input"))
    )
    (net (code "144") (name "/SYNCM") (class "Default")
      (node (ref "U1") (pin "K14") (pinfunction "TR_BF_SYNCM_K14") (pintype "input"))
    )
    (net (code "145") (name "/SYNCP") (class "Default")
      (node (ref "U1") (pin "K13") (pinfunction "TR_BF_SYNCP_K13") (pintype "input"))
    )
    (net (code "146") (name "/TSHUT") (class "Default")
      (node (ref "J7") (pin "2") (pinfunction "2_2") (pintype "passive"))
      (node (ref "U1") (pin "D8") (pinfunction "TSHUT_D8") (pintype "passive"))
    )
    (net (code "147") (name "/TSHUT_FUNC") (class "Default")
      (node (ref "J7") (pin "1") (pinfunction "1_1") (pintype "passive"))
      (node (ref "R43") (pin "1") (pinfunction "1_1") (pintype "passive"))
    )
    (net (code "148") (name "/TX_CLKM") (class "Default")
      (node (ref "C27") (pin "2") (pinfunction "2_2") (pintype "passive"))
    )
    (net (code "149") (name "/TX_CLKP") (class "Default")
      (node (ref "C26") (pin "2") (pinfunction "2_2") (pintype "passive"))
    )
    (net (code "150") (name "/TX_RXZ") (class "Default")
      (node (ref "J13") (pin "2") (pinfunction "2_2") (pintype "passive"))
      (node (ref "U1") (pin "C9") (pinfunction "TX_RXZ_C9") (pintype "output"))
    )
    (net (code "151") (name "/TX_RXZ_FUNC") (class "Default")
      (node (ref "J13") (pin "1") (pinfunction "1_1") (pintype "passive"))
      (node (ref "R44") (pin "1") (pinfunction "1_1") (pintype "passive"))
    )
    (net (code "152") (name "/WAKE_UP") (class "Default")
      (node (ref "R419") (pin "1") (pinfunction "1_1") (pintype "passive"))
      (node (ref "R423") (pin "2") (pinfunction "2_2") (pintype "passive"))
      (node (ref "U1") (pin "M9") (pinfunction "WAKE_UP_M9") (pintype "passive"))
    )
    (net (code "153") (name "AVDD_IO") (class "Default")
      (node (ref "C68") (pin "1") (pinfunction "1_1") (pintype "passive"))
      (node (ref "C69") (pin "1") (pinfunction "1_1") (pintype "passive"))
      (node (ref "R419") (pin "2") (pinfunction "2_2") (pintype "passive"))
      (node (ref "R420") (pin "2") (pinfunction "2_2") (pintype "passive"))
      (node (ref "R421") (pin "2") (pinfunction "2_2") (pintype "passive"))
      (node (ref "R422") (pin "2") (pinfunction "2_2") (pintype "passive"))
      (node (ref "U1") (pin "G5") (pinfunction "AVDDP_1P8_G5") (pintype "power_in"))
      (node (ref "U1") (pin "H5") (pinfunction "AVDDP_1P8_H5") (pintype "power_in"))
    )
    (net (code "154") (name "GND") (class "Default")
      (node (ref "C28") (pin "2") (pinfunction "2_2") (pintype "passive"))
      (node (ref "C38") (pin "2") (pinfunction "2_2") (pintype "passive"))
      (node (ref "C39") (pin "2") (pinfunction "2_2") (pintype "passive"))
      (node (ref "C40") (pin "2") (pinfunction "2_2") (pintype "passive"))
      (node (ref "C41") (pin "2") (pinfunction "2_2") (pintype "passive"))
      (node (ref "C42") (pin "2") (pinfunction "2_2") (pintype "passive"))
      (node (ref "C43") (pin "2") (pinfunction "2_2") (pintype "passive"))
      (node (ref "C44") (pin "2") (pinfunction "2_2") (pintype "passive"))
      (node (ref "C45") (pin "2") (pinfunction "2_2") (pintype "passive"))
      (node (ref "C47") (pin "2") (pinfunction "2_2") (pintype "passive"))
      (node (ref "C48") (pin "2") (pinfunction "2_2") (pintype "passive"))
      (node (ref "C51") (pin "2") (pinfunction "2_2") (pintype "passive"))
      (node (ref "C52") (pin "2") (pinfunction "2_2") (pintype "passive"))
      (node (ref "C54") (pin "2") (pinfunction "2_2") (pintype "passive"))
      (node (ref "C55") (pin "2") (pinfunction "2_2") (pintype "passive"))
      (node (ref "C56") (pin "2") (pinfunction "2_2") (pintype "passive"))
      (node (ref "C57") (pin "2") (pinfunction "2_2") (pintype "passive"))
      (node (ref "C58") (pin "2") (pinfunction "2_2") (pintype "passive"))
      (node (ref "C59") (pin "2") (pinfunction "2_2") (pintype "passive"))
      (node (ref "C60") (pin "2") (pinfunction "2_2") (pintype "passive"))
      (node (ref "C61") (pin "2") (pinfunction "2_2") (pintype "passive"))
      (node (ref "C62") (pin "2") (pinfunction "2_2") (pintype "passive"))
      (node (ref "C66") (pin "2") (pinfunction "2_2") (pintype "passive"))
      (node (ref "C67") (pin "2") (pinfunction "2_2") (pintype "passive"))
      (node (ref "C68") (pin "2") (pinfunction "2_2") (pintype "passive"))
      (node (ref "C69") (pin "2") (pinfunction "2_2") (pintype "passive"))
      (node (ref "D1") (pin "2") (pinfunction "K_2") (pintype "passive"))
      (node (ref "D12") (pin "2") (pinfunction "K_2") (pintype "passive"))
      (node (ref "D4") (pin "2") (pinfunction "K_2") (pintype "passive"))
      (node (ref "R423") (pin "1") (pinfunction "1_1") (pintype "passive"))
      (node (ref "R424") (pin "1") (pinfunction "1_1") (pintype "passive"))
      (node (ref "R425") (pin "1") (pinfunction "1_1") (pintype "passive"))
      (node (ref "R426") (pin "1") (pinfunction "1_1") (pintype "passive"))
      (node (ref "TP28") (pin "1") (pintype "passive"))
      (node (ref "TP40") (pin "1") (pintype "passive"))
      (node (ref "TP41") (pin "1") (pintype "passive"))
      (node (ref "U1") (pin "E10") (pinfunction "AVSS_DAMP_E10") (pintype "power_in"))
      (node (ref "U1") (pin "E11") (pinfunction "AVSS_DAMP_E11") (pintype "power_in"))
      (node (ref "U1") (pin "E4") (pinfunction "AVSS_DAMP_E4") (pintype "power_in"))
      (node (ref "U1") (pin "E6") (pinfunction "AVSS_DAMP_E6") (pintype "power_in"))
      (node (ref "U1") (pin "F4") (pinfunction "AVSS_F4") (pintype "power_in"))
      (node (ref "U1") (pin "F6") (pinfunction "AVSS_F6") (pintype "power_in"))
      (node (ref "U1") (pin "G10") (pinfunction "AVSS_G10") (pintype "power_in"))
      (node (ref "U1") (pin "G4") (pinfunction "AVSS_G4") (pintype "power_in"))
      (node (ref "U1") (pin "H10") (pinfunction "AVSS_H10") (pintype "power_in"))
      (node (ref "U1") (pin "H4") (pinfunction "AVSS_H4") (pintype "power_in"))
      (node (ref "U1") (pin "J4") (pinfunction "AVSS_J4") (pintype "power_in"))
      (node (ref "U1") (pin "J6") (pinfunction "AVSS_J6") (pintype "power_in"))
      (node (ref "U1") (pin "K10") (pinfunction "AVSS_DAMP_K10") (pintype "power_in"))
      (node (ref "U1") (pin "K11") (pinfunction "AVSS_DAMP_K11") (pintype "power_in"))
      (node (ref "U1") (pin "K4") (pinfunction "AVSS_DAMP_K4") (pintype "power_in"))
      (node (ref "U1") (pin "K6") (pinfunction "AVSS_DAMP_K6") (pintype "power_in"))
    )
    (net (code "155") (name "MHV") (class "Default")
      (node (ref "C57") (pin "1") (pinfunction "1_1") (pintype "passive"))
      (node (ref "C58") (pin "1") (pinfunction "1_1") (pintype "passive"))
      (node (ref "C59") (pin "1") (pinfunction "1_1") (pintype "passive"))
      (node (ref "C60") (pin "1") (pinfunction "1_1") (pintype "passive"))
      (node (ref "C61") (pin "1") (pinfunction "1_1") (pintype "passive"))
      (node (ref "C62") (pin "1") (pinfunction "1_1") (pintype "passive"))
      (node (ref "C66") (pin "1") (pinfunction "1_1") (pintype "passive"))
      (node (ref "C67") (pin "1") (pinfunction "1_1") (pintype "passive"))
      (node (ref "U1") (pin "C1") (pinfunction "AVDDM_HV_C1") (pintype "power_in"))
      (node (ref "U1") (pin "C2") (pinfunction "AVDDM_HV_C2") (pintype "power_in"))
      (node (ref "U1") (pin "C3") (pinfunction "AVDDM_HV_C3") (pintype "power_in"))
      (node (ref "U1") (pin "C4") (pinfunction "AVDDM_HV_C4") (pintype "power_in"))
      (node (ref "U1") (pin "D1") (pinfunction "AVDDM_HV_D1") (pintype "power_in"))
      (node (ref "U1") (pin "D2") (pinfunction "AVDDM_HV_D2") (pintype "power_in"))
      (node (ref "U1") (pin "D3") (pinfunction "AVDDM_HV_D3") (pintype "power_in"))
      (node (ref "U1") (pin "D4") (pinfunction "AVDDM_HV_D4") (pintype "power_in"))
      (node (ref "U1") (pin "L1") (pinfunction "AVDDM_HV_L1") (pintype "power_in"))
      (node (ref "U1") (pin "L2") (pinfunction "AVDDM_HV_L2") (pintype "power_in"))
      (node (ref "U1") (pin "L3") (pinfunction "AVDDM_HV_L3") (pintype "power_in"))
      (node (ref "U1") (pin "L4") (pinfunction "AVDDM_HV_L4") (pintype "power_in"))
      (node (ref "U1") (pin "M1") (pinfunction "AVDDM_HV_M1") (pintype "power_in"))
      (node (ref "U1") (pin "M2") (pinfunction "AVDDM_HV_M2") (pintype "power_in"))
      (node (ref "U1") (pin "M3") (pinfunction "AVDDM_HV_M3") (pintype "power_in"))
      (node (ref "U1") (pin "M4") (pinfunction "AVDDM_HV_M4") (pintype "power_in"))
    )
    (net (code "156") (name "Net-(D1-A)") (class "Default")
      (node (ref "D1") (pin "1") (pinfunction "A_1") (pintype "passive"))
      (node (ref "R43") (pin "2") (pinfunction "2_2") (pintype "passive"))
    )
    (net (code "157") (name "Net-(D4-A)") (class "Default")
      (node (ref "D4") (pin "1") (pinfunction "A_1") (pintype "passive"))
      (node (ref "R44") (pin "2") (pinfunction "2_2") (pintype "passive"))
    )
    (net (code "158") (name "Net-(D12-A)") (class "Default")
      (node (ref "D12") (pin "1") (pinfunction "A_1") (pintype "passive"))
      (node (ref "R45") (pin "2") (pinfunction "2_2") (pintype "passive"))
    )
    (net (code "159") (name "Net-(J7-Pad3)") (class "Default")
      (node (ref "J7") (pin "3") (pinfunction "3_3") (pintype "passive"))
      (node (ref "TP18") (pin "1") (pintype "passive"))
    )
    (net (code "160") (name "Net-(J13-Pad3)") (class "Default")
      (node (ref "J13") (pin "3") (pinfunction "3_3") (pintype "passive"))
      (node (ref "TP42") (pin "1") (pintype "passive"))
    )
    (net (code "161") (name "Net-(J16-Pad3)") (class "Default")
      (node (ref "J16") (pin "3") (pinfunction "3_3") (pintype "passive"))
      (node (ref "TP54") (pin "1") (pintype "passive"))
    )
    (net (code "162") (name "Net-(U1A-BF_CLKM)") (class "Default")
      (node (ref "C27") (pin "1") (pinfunction "1_1") (pintype "passive"))
      (node (ref "U1") (pin "J14") (pinfunction "BF_CLKM_J14") (pintype "input"))
    )
    (net (code "163") (name "Net-(U1A-BF_CLKP)") (class "Default")
      (node (ref "C26") (pin "1") (pinfunction "1_1") (pintype "passive"))
      (node (ref "U1") (pin "J13") (pinfunction "BF_CLKP_J13") (pintype "input"))
    )
    (net (code "164") (name "PHV") (class "Default")
      (node (ref "C28") (pin "1") (pinfunction "1_1") (pintype "passive"))
      (node (ref "C38") (pin "1") (pinfunction "1_1") (pintype "passive"))
      (node (ref "C39") (pin "1") (pinfunction "1_1") (pintype "passive"))
      (node (ref "C40") (pin "1") (pinfunction "1_1") (pintype "passive"))
      (node (ref "C41") (pin "1") (pinfunction "1_1") (pintype "passive"))
      (node (ref "C42") (pin "1") (pinfunction "1_1") (pintype "passive"))
      (node (ref "C43") (pin "1") (pinfunction "1_1") (pintype "passive"))
      (node (ref "C44") (pin "1") (pinfunction "1_1") (pintype "passive"))
      (node (ref "U1") (pin "A4") (pinfunction "AVDDP_HV_A4") (pintype "power_in"))
      (node (ref "U1") (pin "A5") (pinfunction "AVDDP_HV_A5") (pintype "power_in"))
      (node (ref "U1") (pin "A6") (pinfunction "AVDDP_HV_A6") (pintype "power_in"))
      (node (ref "U1") (pin "A7") (pinfunction "AVDDP_HV_A7") (pintype "power_in"))
      (node (ref "U1") (pin "P4") (pinfunction "AVDDP_HV_P4") (pintype "power_in"))
      (node (ref "U1") (pin "P5") (pinfunction "AVDDP_HV_P5") (pintype "power_in"))
      (node (ref "U1") (pin "P6") (pinfunction "AVDDP_HV_P6") (pintype "power_in"))
      (node (ref "U1") (pin "P7") (pinfunction "AVDDP_HV_P7") (pintype "power_in"))
    )
    (net (code "165") (name "VDDM_LV5") (class "Default")
      (node (ref "C52") (pin "1") (pinfunction "1_1") (pintype "passive"))
      (node (ref "C54") (pin "1") (pinfunction "1_1") (pintype "passive"))
      (node (ref "C55") (pin "1") (pinfunction "1_1") (pintype "passive"))
      (node (ref "C56") (pin "1") (pinfunction "1_1") (pintype "passive"))
      (node (ref "U1") (pin "F7") (pinfunction "AVDDM_5_F7") (pintype "power_in"))
      (node (ref "U1") (pin "J7") (pinfunction "AVDDM_5_J7") (pintype "power_in"))
    )
    (net (code "166") (name "VDDP_LV5") (class "Default")
      (node (ref "C45") (pin "1") (pinfunction "1_1") (pintype "passive"))
      (node (ref "C47") (pin "1") (pinfunction "1_1") (pintype "passive"))
      (node (ref "C48") (pin "1") (pinfunction "1_1") (pintype "passive"))
      (node (ref "C51") (pin "1") (pinfunction "1_1") (pintype "passive"))
      (node (ref "U1") (pin "F5") (pinfunction "AVDDP_5_F5") (pintype "power_in"))
      (node (ref "U1") (pin "J5") (pinfunction "AVDDP_5_J5") (pintype "power_in"))
    )
    (net (code "167") (name "unconnected-(U1C-NC-PadK8)") (class "Default")
      (node (ref "U1") (pin "K8") (pinfunction "NC_K8") (pintype "passive+no_connect"))
    )
  )
)
